# moodlight.net
KiCad netlist of a schematic drawn in EAGLE
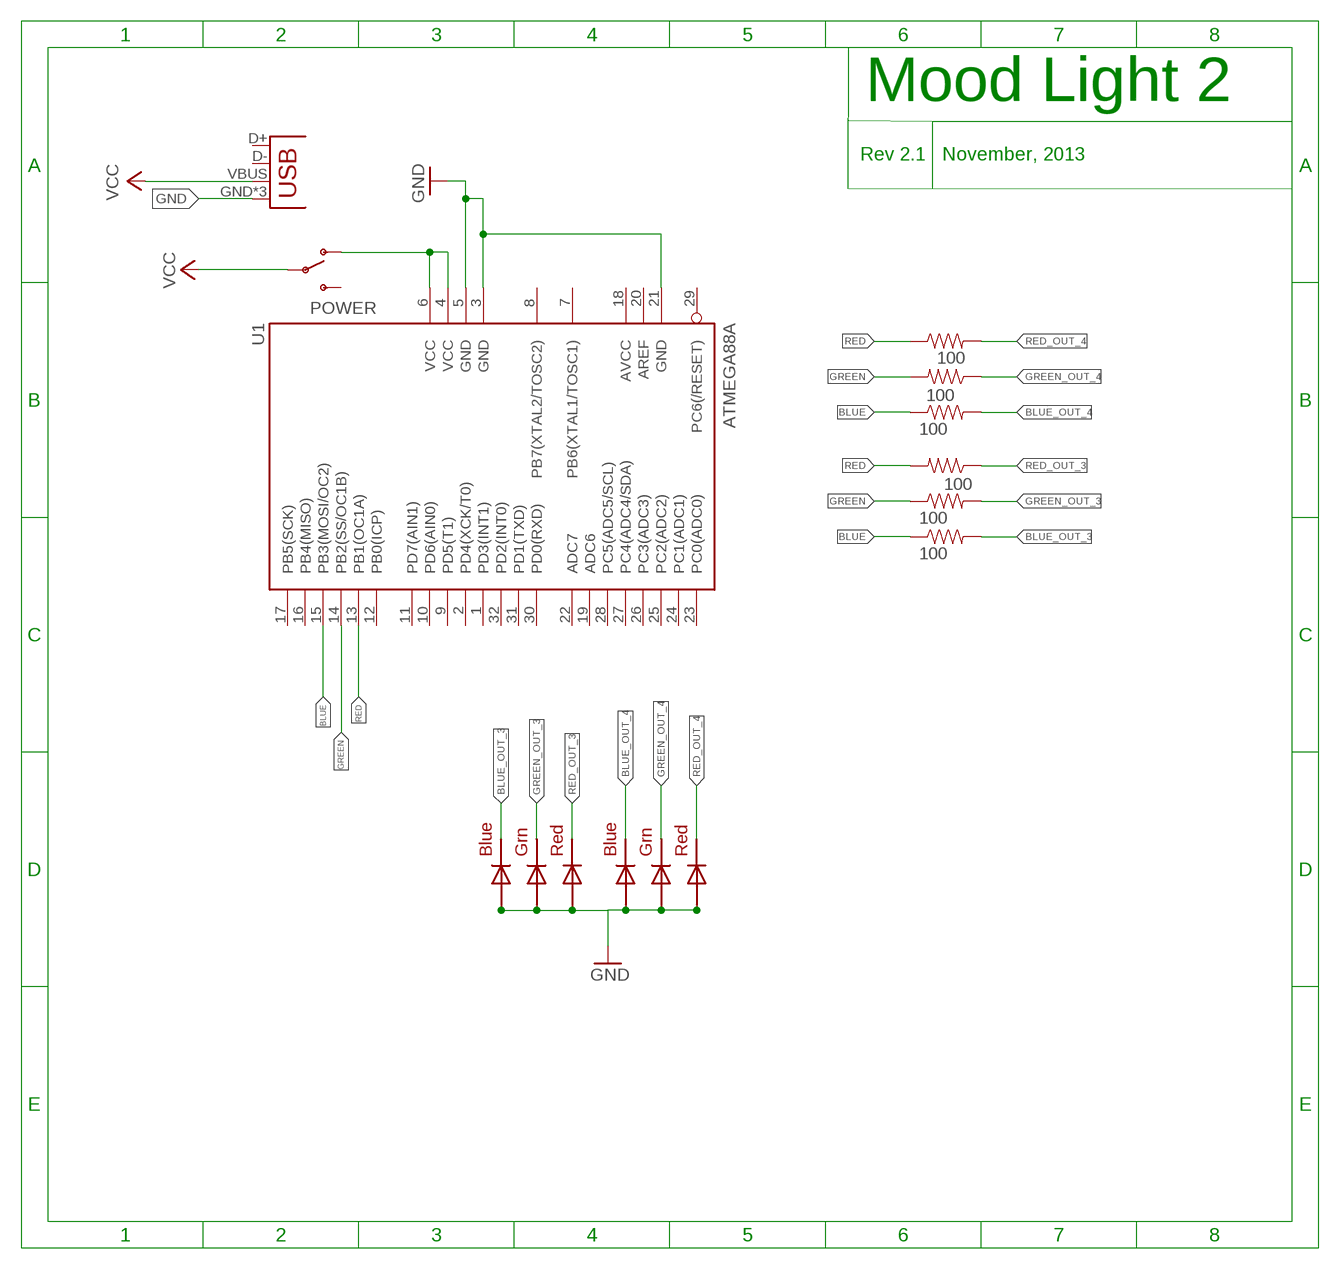
[diagram p0: schematic, sheet 1]

(export (version "E")
  (design (tool "Eeschema 10.0.6"))
  (components
    (comp (ref "JP2")
      (value "USB-MICROB")
      (footprint "eagle-import:USB-MICROB")
      (libsource (lib "eagle-import") (part "USB-MICROB"))
    )
    (comp (ref "LED3")
      (value "RGBLED5050")
      (footprint "eagle-import:RGBLED5050")
      (libsource (lib "eagle-import") (part "RGBLED5050"))
    )
    (comp (ref "LED4")
      (value "RGBLED5050")
      (footprint "eagle-import:RGBLED5050")
      (libsource (lib "eagle-import") (part "RGBLED5050"))
    )
    (comp (ref "POWER")
      (value "5V")
      (footprint "eagle-import:SWITCH-SPDT")
      (libsource (lib "eagle-import") (part "SWITCH-SPDTPTH"))
    )
    (comp (ref "R1")
      (value "100")
      (footprint "eagle-import:0603-RES")
      (libsource (lib "eagle-import") (part "220-5%"))
    )
    (comp (ref "R2")
      (value "100")
      (footprint "eagle-import:0603-RES")
      (libsource (lib "eagle-import") (part "220-5%"))
    )
    (comp (ref "R3")
      (value "100")
      (footprint "eagle-import:0603-RES")
      (libsource (lib "eagle-import") (part "220-5%"))
    )
    (comp (ref "R4")
      (value "100")
      (footprint "eagle-import:0603-RES")
      (libsource (lib "eagle-import") (part "220-5%"))
    )
    (comp (ref "R5")
      (value "100")
      (footprint "eagle-import:0603-RES")
      (libsource (lib "eagle-import") (part "220-5%"))
    )
    (comp (ref "R6")
      (value "100")
      (footprint "eagle-import:0603-RES")
      (libsource (lib "eagle-import") (part "220-5%"))
    )
    (comp (ref "U1")
      (value "ATMEGA88A")
      (footprint "eagle-import:TQFP32-08")
      (fields (field (name "MPN") "ATMEGA8-16AU"))
      (libsource (lib "eagle-import") (part "MEGA8-AI"))
    )
  )
  (nets
    (net (code "1") (name "/AVCC") (class "Default")
      (node (ref "U1") (pin "18") (pinfunction "AVCC_18") (pintype "power_in"))
    )
    (net (code "2") (name "BLUE") (class "Default")
      (node (ref "R3") (pin "1") (pinfunction "1_1") (pintype "passive"))
      (node (ref "R6") (pin "1") (pinfunction "1_1") (pintype "passive"))
      (node (ref "U1") (pin "15") (pinfunction "PB3(MOSI/OC2)_15") (pintype "bidirectional"))
    )
    (net (code "3") (name "BLUE_OUT_3") (class "Default")
      (node (ref "LED3") (pin "4") (pinfunction "BLUE_C_4") (pintype "bidirectional"))
      (node (ref "R6") (pin "2") (pinfunction "2_2") (pintype "passive"))
    )
    (net (code "4") (name "BLUE_OUT_4") (class "Default")
      (node (ref "LED4") (pin "4") (pinfunction "BLUE_C_4") (pintype "bidirectional"))
      (node (ref "R3") (pin "2") (pinfunction "2_2") (pintype "passive"))
    )
    (net (code "5") (name "GND") (class "Default")
      (node (ref "JP2") (pin "GND") (pinfunction "GND_GND") (pintype "bidirectional"))
      (node (ref "JP2") (pin "MT1") (pinfunction "GND_MT1") (pintype "bidirectional"))
      (node (ref "JP2") (pin "MT2") (pinfunction "GND_MT2") (pintype "bidirectional"))
      (node (ref "LED3") (pin "1") (pinfunction "GREEN_A_1") (pintype "bidirectional"))
      (node (ref "LED3") (pin "2") (pinfunction "RED_A_2") (pintype "bidirectional"))
      (node (ref "LED3") (pin "3") (pinfunction "BLUE_A_3") (pintype "bidirectional"))
      (node (ref "LED4") (pin "1") (pinfunction "GREEN_A_1") (pintype "bidirectional"))
      (node (ref "LED4") (pin "2") (pinfunction "RED_A_2") (pintype "bidirectional"))
      (node (ref "LED4") (pin "3") (pinfunction "BLUE_A_3") (pintype "bidirectional"))
      (node (ref "U1") (pin "21") (pinfunction "GND_21") (pintype "power_in"))
      (node (ref "U1") (pin "3") (pinfunction "GND_3") (pintype "power_in"))
      (node (ref "U1") (pin "5") (pinfunction "GND_5") (pintype "power_in"))
    )
    (net (code "6") (name "GREEN") (class "Default")
      (node (ref "R2") (pin "2") (pinfunction "2_2") (pintype "passive"))
      (node (ref "R5") (pin "1") (pinfunction "1_1") (pintype "passive"))
      (node (ref "U1") (pin "14") (pinfunction "PB2(SS/OC1B)_14") (pintype "bidirectional"))
    )
    (net (code "7") (name "GREEN_OUT_3") (class "Default")
      (node (ref "LED3") (pin "6") (pinfunction "GREEN_C_6") (pintype "bidirectional"))
      (node (ref "R5") (pin "2") (pinfunction "2_2") (pintype "passive"))
    )
    (net (code "8") (name "GREEN_OUT_4") (class "Default")
      (node (ref "LED4") (pin "6") (pinfunction "GREEN_C_6") (pintype "bidirectional"))
      (node (ref "R2") (pin "1") (pinfunction "1_1") (pintype "passive"))
    )
    (net (code "9") (name "Net-(POWER-O)") (class "Default")
      (node (ref "POWER") (pin "1") (pinfunction "O_1") (pintype "passive"))
      (node (ref "U1") (pin "4") (pinfunction "VCC_4") (pintype "power_in"))
      (node (ref "U1") (pin "6") (pinfunction "VCC_6") (pintype "power_in"))
    )
    (net (code "10") (name "RED") (class "Default")
      (node (ref "R1") (pin "1") (pinfunction "1_1") (pintype "passive"))
      (node (ref "R4") (pin "2") (pinfunction "2_2") (pintype "passive"))
      (node (ref "U1") (pin "13") (pinfunction "PB1(OC1A)_13") (pintype "bidirectional"))
    )
    (net (code "11") (name "RED_OUT_3") (class "Default")
      (node (ref "LED3") (pin "5") (pinfunction "RED_C_5") (pintype "bidirectional"))
      (node (ref "R4") (pin "1") (pinfunction "1_1") (pintype "passive"))
    )
    (net (code "12") (name "RED_OUT_4") (class "Default")
      (node (ref "LED4") (pin "5") (pinfunction "RED_C_5") (pintype "bidirectional"))
      (node (ref "R1") (pin "2") (pinfunction "2_2") (pintype "passive"))
    )
    (net (code "13") (name "VCC") (class "Default")
      (node (ref "JP2") (pin "VBUS") (pinfunction "VBUS_VBUS") (pintype "bidirectional"))
      (node (ref "POWER") (pin "2") (pinfunction "P_2") (pintype "passive"))
    )
    (net (code "14") (name "unconnected-(JP2-PadD+)") (class "Default")
      (node (ref "JP2") (pin "D+") (pinfunction "D+_D+") (pintype "bidirectional"))
    )
    (net (code "15") (name "unconnected-(JP2-PadD-)") (class "Default")
      (node (ref "JP2") (pin "D-") (pinfunction "D-_D-") (pintype "bidirectional"))
    )
    (net (code "16") (name "unconnected-(POWER-S-Pad3)") (class "Default")
      (node (ref "POWER") (pin "3") (pinfunction "S_3") (pintype "passive"))
    )
    (net (code "17") (name "unconnected-(U1-ADC6-Pad19)") (class "Default")
      (node (ref "U1") (pin "19") (pinfunction "ADC6_19") (pintype "bidirectional"))
    )
    (net (code "18") (name "unconnected-(U1-ADC7-Pad22)") (class "Default")
      (node (ref "U1") (pin "22") (pinfunction "ADC7_22") (pintype "bidirectional"))
    )
    (net (code "19") (name "unconnected-(U1-AREF-Pad20)") (class "Default")
      (node (ref "U1") (pin "20") (pinfunction "AREF_20") (pintype "passive"))
    )
    (net (code "20") (name "unconnected-(U1-PB0(ICP)-Pad12)") (class "Default")
      (node (ref "U1") (pin "12") (pinfunction "PB0(ICP)_12") (pintype "bidirectional"))
    )
    (net (code "21") (name "unconnected-(U1-PB4(MISO)-Pad16)") (class "Default")
      (node (ref "U1") (pin "16") (pinfunction "PB4(MISO)_16") (pintype "bidirectional"))
    )
    (net (code "22") (name "unconnected-(U1-PB5(SCK)-Pad17)") (class "Default")
      (node (ref "U1") (pin "17") (pinfunction "PB5(SCK)_17") (pintype "bidirectional"))
    )
    (net (code "23") (name "unconnected-(U1-PB6(XTAL1{slash}TOSC1)-Pad7)") (class "Default")
      (node (ref "U1") (pin "7") (pinfunction "PB6(XTAL1/TOSC1)_7") (pintype "bidirectional"))
    )
    (net (code "24") (name "unconnected-(U1-PB7(XTAL2{slash}TOSC2)-Pad8)") (class "Default")
      (node (ref "U1") (pin "8") (pinfunction "PB7(XTAL2/TOSC2)_8") (pintype "bidirectional"))
    )
    (net (code "25") (name "unconnected-(U1-PC0(ADC0)-Pad23)") (class "Default")
      (node (ref "U1") (pin "23") (pinfunction "PC0(ADC0)_23") (pintype "bidirectional"))
    )
    (net (code "26") (name "unconnected-(U1-PC1(ADC1)-Pad24)") (class "Default")
      (node (ref "U1") (pin "24") (pinfunction "PC1(ADC1)_24") (pintype "bidirectional"))
    )
    (net (code "27") (name "unconnected-(U1-PC2(ADC2)-Pad25)") (class "Default")
      (node (ref "U1") (pin "25") (pinfunction "PC2(ADC2)_25") (pintype "bidirectional"))
    )
    (net (code "28") (name "unconnected-(U1-PC3(ADC3)-Pad26)") (class "Default")
      (node (ref "U1") (pin "26") (pinfunction "PC3(ADC3)_26") (pintype "bidirectional"))
    )
    (net (code "29") (name "unconnected-(U1-PC4(ADC4{slash}SDA)-Pad27)") (class "Default")
      (node (ref "U1") (pin "27") (pinfunction "PC4(ADC4/SDA)_27") (pintype "bidirectional"))
    )
    (net (code "30") (name "unconnected-(U1-PC5(ADC5{slash}SCL)-Pad28)") (class "Default")
      (node (ref "U1") (pin "28") (pinfunction "PC5(ADC5/SCL)_28") (pintype "bidirectional"))
    )
    (net (code "31") (name "unconnected-(U1-PC6({slash}RESET)-Pad29)") (class "Default")
      (node (ref "U1") (pin "29") (pinfunction "PC6(/RESET)_29") (pintype "bidirectional"))
    )
    (net (code "32") (name "unconnected-(U1-PD0(RXD)-Pad30)") (class "Default")
      (node (ref "U1") (pin "30") (pinfunction "PD0(RXD)_30") (pintype "bidirectional"))
    )
    (net (code "33") (name "unconnected-(U1-PD1(TXD)-Pad31)") (class "Default")
      (node (ref "U1") (pin "31") (pinfunction "PD1(TXD)_31") (pintype "bidirectional"))
    )
    (net (code "34") (name "unconnected-(U1-PD2(INT0)-Pad32)") (class "Default")
      (node (ref "U1") (pin "32") (pinfunction "PD2(INT0)_32") (pintype "bidirectional"))
    )
    (net (code "35") (name "unconnected-(U1-PD3(INT1)-Pad1)") (class "Default")
      (node (ref "U1") (pin "1") (pinfunction "PD3(INT1)_1") (pintype "bidirectional"))
    )
    (net (code "36") (name "unconnected-(U1-PD4(XCK{slash}T0)-Pad2)") (class "Default")
      (node (ref "U1") (pin "2") (pinfunction "PD4(XCK/T0)_2") (pintype "bidirectional"))
    )
    (net (code "37") (name "unconnected-(U1-PD5(T1)-Pad9)") (class "Default")
      (node (ref "U1") (pin "9") (pinfunction "PD5(T1)_9") (pintype "bidirectional"))
    )
    (net (code "38") (name "unconnected-(U1-PD6(AIN0)-Pad10)") (class "Default")
      (node (ref "U1") (pin "10") (pinfunction "PD6(AIN0)_10") (pintype "bidirectional"))
    )
    (net (code "39") (name "unconnected-(U1-PD7(AIN1)-Pad11)") (class "Default")
      (node (ref "U1") (pin "11") (pinfunction "PD7(AIN1)_11") (pintype "bidirectional"))
    )
  )
)
